# Schematic1.net
KiCad netlist of a schematic drawn in Altium Designer
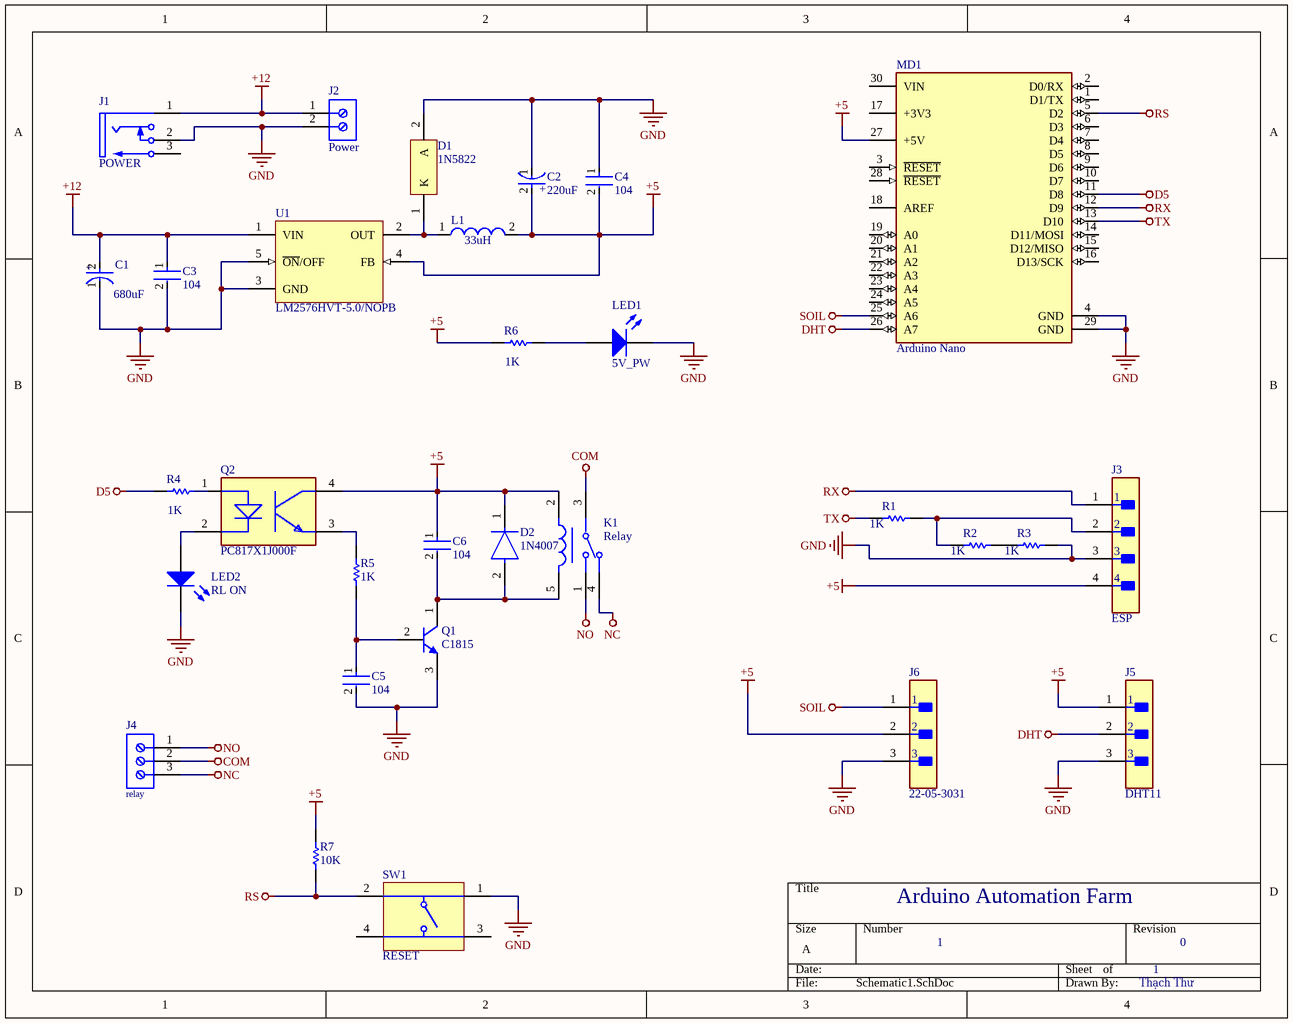
[diagram p0: Schematic1.SchDoc]

(export (version "E")
  (design (tool "Eeschema 10.0.6"))
  (components
    (comp (ref "C1")
      (value "680uF")
      (footprint "FP-RAD-TH-D_12_5_0_5-L_30-MFG")
      (description "Aluminum Electrolytic Capacitors (Radial Lead Type) AEC-Q200 Qualified 680uF ±20% 50V")
      (fields (field (name "VOLTAGE") "50V") (field (name "TOLERANCE") "20%"))
      (libsource (lib "Altium Content Vault") (part "203bc49f2ac43e59fd269a8c329ed05"))
    )
    (comp (ref "C2")
      (value "220uF")
      (footprint "FP-RAD-TH-D_8_0_5-L_11_5-MFG")
      (description "Aluminum Electrolytic Capacitors (Radial Lead Type) 220uF ±20% 25V")
      (fields (field (name "VOLTAGE") "25V") (field (name "TOLERANCE") "20%"))
      (libsource (lib "Altium Content Vault") (part "a00bbbee19879c290e62620ae7e47b1"))
    )
    (comp (ref "C3")
      (value "104")
      (footprint "FP-RCE1A2-MFG")
      (description "Cap Ceramic 100nF 100V X7R ±10% Radial 2.5mm +125°C Automotive Ammo Pack")
      (fields (field (name "TOLERANCE") "10%"))
      (libsource (lib "Altium Content Vault") (part "02cd4be3c70576c341d710602a673aa"))
    )
    (comp (ref "C4")
      (value "104")
      (footprint "FP-RCE1A2-MFG")
      (description "Cap Ceramic 100nF 100V X7R ±10% Radial 2.5mm +125°C Automotive Ammo Pack")
      (fields (field (name "TOLERANCE") "10%"))
      (libsource (lib "Altium Content Vault") (part "02cd4be3c70576c341d710602a673aa"))
    )
    (comp (ref "C5")
      (value "104")
      (footprint "FP-RCE1A2-MFG")
      (description "Cap Ceramic 100nF 100V X7R ±10% Radial 2.5mm +125°C Automotive Ammo Pack")
      (fields (field (name "TOLERANCE") "10%"))
      (libsource (lib "Altium Content Vault") (part "02cd4be3c70576c341d710602a673aa"))
    )
    (comp (ref "C6")
      (value "104")
      (footprint "FP-RCE1A2-MFG")
      (description "Cap Ceramic 100nF 100V X7R ±10% Radial 2.5mm +125°C Automotive Ammo Pack")
      (fields (field (name "TOLERANCE") "10%"))
      (libsource (lib "Altium Content Vault") (part "02cd4be3c70576c341d710602a673aa"))
    )
    (comp (ref "D1")
      (value "1N5822")
      (footprint "ONSC-AXIAL_LEAD-2-267-05_V")
      (description "Rectifier, 2-Pin Axial_Lead, Bulk Bag")
      (fields (field (name "MANUFACTURER") "On Semiconductor"))
      (libsource (lib "Altium Content Vault") (part "ONSC-D-K1A2-2_A"))
    )
    (comp (ref "D2")
      (value "1N4007")
      (footprint "FP-1N4007-MFG")
      (description "Rectifier diode 1000 V 1 A DO-41, ,")
      (fields
        (field (name "MANUFACTURER") "Diotec")
        (field (name "OCTOPART") "https://octopart.com/1n4007-diotec-4040411")
      )
      (libsource (lib "Altium Content Vault") (part "d7152d700b627762746794eb795d46e"))
    )
    (comp (ref "J1")
      (value "POWER")
      (footprint "SWITCH-RAPC712X-3_V")
      (description "Conn Powerjack Mini R/A PCMT, 5 A, 3-Pin THD, RoHS")
      (fields (field (name "MANUFACTURER") "Switchcraft"))
      (libsource (lib "Altium Content Vault") (part "SWITCH-RAPC712X-3"))
    )
    (comp (ref "J2")
      (value "Power")
      (footprint "691102710002")
      (description "Series 102 - 5.00 mm Horizontal Entry Modular with Pressure Clamp WR-TBL, 2 pin")
      (fields
        (field (name "MANUFACTURER") "Wurth Elektronik")
        (field (name "PART NUMBER") "691102710002")
        (field (name "PUBLISHER") "WurthElektronik")
      )
      (libsource (lib "Altium Content Vault") (part "WE-CN-1P-F-TB2"))
    )
    (comp (ref "J3")
      (value "ESP")
      (footprint "FP-110990030-MFG")
      (description "GROVE 2MM 4PIN VERT CONN 10PCS")
      (libsource (lib "Altium Content Vault") (part "299a8cea1bdcbc3624fe62c390fa72c"))
    )
    (comp (ref "J4")
      (value "relay")
      (footprint "691101710003")
      (description "Series 101 - 5.00 mm Horizontal Entry Modular with Pressure Clamp WR-TBL, 3 pin")
      (fields
        (field (name "PART NUMBER") "691101710003")
        (field (name "MANUFACTURER") "Wurth Elektronik")
        (field (name "PUBLISHER") "WurthElektronik")
      )
      (libsource (lib "Altium Content Vault") (part "WE-CN-1P-F-TB3"))
    )
    (comp (ref "J5")
      (value "DHT11")
      (footprint "FP-22-28-4030-MFG")
      (description "CONN HEADER VERT 3POS 2.54MM")
      (fields
        (field (name "MANUFACTURER PART NUMBER") "22-28-4030")
        (field (name "OCTOPART") "https://octopart.com/0022284030-molex-10476094")
      )
      (libsource (lib "Altium Content Vault") (part "0d3f023dd272f625e17a2be33dea85f"))
    )
    (comp (ref "J6")
      (value "22-05-3031")
      (footprint "FP-22-05-3031-MFG")
      (description "CONN HEADER R/A 3POS 2.54MM")
      (libsource (lib "Altium Content Vault") (part "0d3f023dd272f625e17a2be33dea85f"))
    )
    (comp (ref "K1")
      (value "Relay")
      (footprint "FP-1-1721150-0-MFG")
      (description "RELAY GEN PURPOSE SPDT 10A 5V")
      (fields
        (field (name "MANUFACTURER") "TE")
        (field (name "OCTOPART") "https://octopart.com/1-1721150-0-te+connectivity-41294869")
      )
      (libsource (lib "Altium Content Vault") (part "6d7f6cec76f9d90da65a396cf24d809"))
    )
    (comp (ref "L1")
      (value "33uH")
      (footprint "WE-TI-L")
      (description "Radial Leaded Wire Wound Inductor WE-TI, L=330 µH")
      (fields (field (name "PARTNUMBER") "744772331") (field (name "MANUFACTURER") "Wuerth Elektronik"))
      (libsource (lib "Altium Content Vault") (part "PAS-IND-INDUCTOR-2"))
    )
    (comp (ref "LED1")
      (value "5V_PW")
      (footprint "Type 5mm")
      (description "THT LED round mono-color color lens, WL-TMRW, Blue")
      (fields (field (name "MANUFACTURER") "Wuerth Elektronik") (field (name "PARTNUMBER") "151051BS04000"))
      (libsource (lib "Altium Content Vault") (part "WE-LED_K1A2-2"))
    )
    (comp (ref "LED2")
      (value "RL ON")
      (footprint "Type 5mm")
      (description "THT LED round mono-color color lens, WL-TMRW, Blue")
      (fields (field (name "MANUFACTURER") "Wuerth Elektronik") (field (name "PARTNUMBER") "151051BS04000"))
      (libsource (lib "Altium Content Vault") (part "WE-LED_K1A2-2"))
    )
    (comp (ref "MD1")
      (value "Arduino Nano")
      (footprint "FP-A000005-MFG")
      (description "ARDUINO NANO ATMEGA328 EVAL BRD")
      (libsource (lib "Altium Content Vault") (part "d190c066e99afd1c6882cf92e11b2cc"))
    )
    (comp (ref "Q1")
      (value "C1815")
      (footprint "TO-226-AA")
      (description "NPN Bipolar Transistor")
      (fields (field (name "PUBLISHER") "Altium Limited"))
      (libsource (lib "Miscellaneous Devices") (part "NPN"))
    )
    (comp (ref "Q2")
      (value "PC817X1J000F")
      (footprint "FP-PC817X1J000F-MFG")
      (description "OPTOISOLATOR 5KV TRANS 4DIP")
      (libsource (lib "Altium Content Vault") (part "8d9d817270a4e8f0d794346117f6aa3"))
    )
    (comp (ref "R1")
      (value "1K")
      (footprint "AXIAL-0.3")
      (description "Resistor")
      (fields (field (name "Comment") "Res1") (field (name "PUBLISHER") "Altium Limited"))
      (libsource (lib "Miscellaneous Devices") (part "Res1"))
    )
    (comp (ref "R2")
      (value "1K")
      (footprint "AXIAL-0.3")
      (description "Resistor")
      (fields (field (name "Comment") "Res1") (field (name "PUBLISHER") "Altium Limited"))
      (libsource (lib "Miscellaneous Devices") (part "Res1"))
    )
    (comp (ref "R3")
      (value "1K")
      (footprint "AXIAL-0.3")
      (description "Resistor")
      (fields (field (name "Comment") "Res1") (field (name "PUBLISHER") "Altium Limited"))
      (libsource (lib "Miscellaneous Devices") (part "Res1"))
    )
    (comp (ref "R4")
      (value "1K")
      (footprint "AXIAL-0.3")
      (description "Resistor")
      (fields (field (name "Comment") "Res1") (field (name "PUBLISHER") "Altium Limited"))
      (libsource (lib "Miscellaneous Devices") (part "Res1"))
    )
    (comp (ref "R5")
      (value "1K")
      (footprint "AXIAL-0.3")
      (description "Resistor")
      (fields (field (name "Comment") "Res1") (field (name "PUBLISHER") "Altium Limited"))
      (libsource (lib "Miscellaneous Devices") (part "Res1"))
    )
    (comp (ref "R6")
      (value "1K")
      (footprint "AXIAL-0.3")
      (description "Resistor")
      (fields (field (name "Comment") "Res1") (field (name "PUBLISHER") "Altium Limited"))
      (libsource (lib "Miscellaneous Devices") (part "Res1"))
    )
    (comp (ref "R7")
      (value "10K")
      (footprint "AXIAL-0.3")
      (description "Resistor")
      (fields (field (name "PUBLISHER") "Altium Limited"))
      (libsource (lib "Miscellaneous Devices") (part "Res1"))
    )
    (comp (ref "SW1")
      (value "RESET")
      (footprint "TECO-1825910-6_V")
      (description "Tact Switch, SPST-NO, 0.05 A, -35 to 85 degC, 4-Pin THD, RoHS, Bulk")
      (fields (field (name "PART NO") "1825910-6") (field (name "MANUFACTURER") "TE Connectivity"))
      (libsource (lib "Altium Content Vault") (part "SW-SPST-4_A"))
    )
    (comp (ref "U1")
      (value "LM2576HVT-5.0/NOPB")
      (footprint "KC0005A")
      (description "SIMPLE SWITCHER® 3A Step-Down Voltage Regulator, 5-pin TO-220, Pb-Free")
      (fields (field (name "MANUFACTURER") "Texas Instruments"))
      (libsource (lib "Altium Content Vault") (part "PM-REG-LM2575HVT-12"))
    )
  )
  (nets
    (net (code "1") (name "+5") (class "Default")
      (node (ref "C2") (pin "2") (pinfunction "A_2") (pintype "passive"))
      (node (ref "C4") (pin "2") (pinfunction "2_2") (pintype "passive"))
      (node (ref "C6") (pin "1") (pinfunction "1_1") (pintype "passive"))
      (node (ref "D2") (pin "1") (pinfunction "C_1") (pintype "passive"))
      (node (ref "J3") (pin "4") (pinfunction "4_4") (pintype "passive"))
      (node (ref "J5") (pin "1") (pinfunction "1_1") (pintype "passive"))
      (node (ref "J6") (pin "2") (pinfunction "2_2") (pintype "passive"))
      (node (ref "K1") (pin "2") (pinfunction "2_2") (pintype "passive"))
      (node (ref "L1") (pin "2") (pinfunction "2_2") (pintype "passive"))
      (node (ref "MD1") (pin "27") (pinfunction "+5V_27") (pintype "power_in"))
      (node (ref "Q2") (pin "4") (pinfunction "C_4") (pintype "passive"))
      (node (ref "R6") (pin "2") (pinfunction "2_2") (pintype "passive"))
      (node (ref "R7") (pin "1") (pinfunction "1_1") (pintype "passive"))
      (node (ref "U1") (pin "4") (pinfunction "FB_4") (pintype "input"))
    )
    (net (code "2") (name "+12") (class "Default")
      (node (ref "C1") (pin "2") (pinfunction "A_2") (pintype "passive"))
      (node (ref "C3") (pin "1") (pinfunction "1_1") (pintype "passive"))
      (node (ref "J1") (pin "1") (pinfunction "1_1") (pintype "passive"))
      (node (ref "J2") (pin "1") (pinfunction "1_1") (pintype "passive"))
      (node (ref "U1") (pin "1") (pinfunction "VIN_1") (pintype "power_in"))
    )
    (net (code "3") (name "COM") (class "Default")
      (node (ref "J4") (pin "2") (pinfunction "2_2") (pintype "passive"))
      (node (ref "K1") (pin "3") (pinfunction "3_3") (pintype "passive"))
    )
    (net (code "4") (name "D5") (class "Default")
      (node (ref "MD1") (pin "11") (pinfunction "D8_11") (pintype "bidirectional"))
      (node (ref "R4") (pin "2") (pinfunction "2_2") (pintype "passive"))
    )
    (net (code "5") (name "DHT") (class "Default")
      (node (ref "J5") (pin "2") (pinfunction "2_2") (pintype "passive"))
      (node (ref "MD1") (pin "26") (pinfunction "A7_26") (pintype "bidirectional"))
    )
    (net (code "6") (name "GND") (class "Default")
      (node (ref "C1") (pin "1") (pinfunction "C_1") (pintype "passive"))
      (node (ref "C2") (pin "1") (pinfunction "C_1") (pintype "passive"))
      (node (ref "C3") (pin "2") (pinfunction "2_2") (pintype "passive"))
      (node (ref "C4") (pin "1") (pinfunction "1_1") (pintype "passive"))
      (node (ref "C5") (pin "2") (pinfunction "2_2") (pintype "passive"))
      (node (ref "D1") (pin "2") (pinfunction "A_2") (pintype "passive"))
      (node (ref "J1") (pin "2") (pinfunction "2_2") (pintype "passive"))
      (node (ref "J2") (pin "2") (pinfunction "2_2") (pintype "passive"))
      (node (ref "J3") (pin "3") (pinfunction "3_3") (pintype "passive"))
      (node (ref "J5") (pin "3") (pinfunction "3_3") (pintype "passive"))
      (node (ref "J6") (pin "3") (pinfunction "3_3") (pintype "passive"))
      (node (ref "LED1") (pin "1") (pinfunction "K_1") (pintype "passive"))
      (node (ref "LED2") (pin "1") (pinfunction "K_1") (pintype "passive"))
      (node (ref "MD1") (pin "29") (pinfunction "GND_29") (pintype "power_in"))
      (node (ref "MD1") (pin "4") (pinfunction "GND_4") (pintype "power_in"))
      (node (ref "Q1") (pin "3") (pinfunction "E_3") (pintype "passive"))
      (node (ref "R3") (pin "1") (pinfunction "1_1") (pintype "passive"))
      (node (ref "SW1") (pin "1") (pinfunction "1_1") (pintype "passive"))
      (node (ref "U1") (pin "3") (pinfunction "GND_3") (pintype "power_in"))
      (node (ref "U1") (pin "5") (pinfunction "~{ON}/OFF_5") (pintype "input"))
    )
    (net (code "7") (name "NC") (class "Default")
      (node (ref "J4") (pin "3") (pinfunction "3_3") (pintype "passive"))
      (node (ref "K1") (pin "4") (pinfunction "4_4") (pintype "passive"))
    )
    (net (code "8") (name "NO") (class "Default")
      (node (ref "J4") (pin "1") (pinfunction "1_1") (pintype "passive"))
      (node (ref "K1") (pin "1") (pinfunction "1_1") (pintype "passive"))
    )
    (net (code "9") (name "Net-(D1-K)") (class "Default")
      (node (ref "D1") (pin "1") (pinfunction "K_1") (pintype "passive"))
      (node (ref "L1") (pin "1") (pinfunction "1_1") (pintype "passive"))
      (node (ref "U1") (pin "2") (pinfunction "OUT_2") (pintype "power_in"))
    )
    (net (code "10") (name "Net-(D2-A)") (class "Default")
      (node (ref "C6") (pin "2") (pinfunction "2_2") (pintype "passive"))
      (node (ref "D2") (pin "2") (pinfunction "A_2") (pintype "passive"))
      (node (ref "K1") (pin "5") (pinfunction "5_5") (pintype "passive"))
      (node (ref "Q1") (pin "1") (pinfunction "C_1") (pintype "passive"))
    )
    (net (code "11") (name "Net-(J3-Pad2)") (class "Default")
      (node (ref "J3") (pin "2") (pinfunction "2_2") (pintype "passive"))
      (node (ref "R1") (pin "1") (pinfunction "1_1") (pintype "passive"))
      (node (ref "R2") (pin "2") (pinfunction "2_2") (pintype "passive"))
    )
    (net (code "12") (name "Net-(LED1-A)") (class "Default")
      (node (ref "LED1") (pin "2") (pinfunction "A_2") (pintype "passive"))
      (node (ref "R6") (pin "1") (pinfunction "1_1") (pintype "passive"))
    )
    (net (code "13") (name "Net-(LED2-A)") (class "Default")
      (node (ref "LED2") (pin "2") (pinfunction "A_2") (pintype "passive"))
      (node (ref "Q2") (pin "2") (pinfunction "C_2") (pintype "passive"))
    )
    (net (code "14") (name "Net-(Q1-B)") (class "Default")
      (node (ref "C5") (pin "1") (pinfunction "1_1") (pintype "passive"))
      (node (ref "Q1") (pin "2") (pinfunction "B_2") (pintype "passive"))
      (node (ref "R5") (pin "2") (pinfunction "2_2") (pintype "passive"))
    )
    (net (code "15") (name "Net-(Q2-A)") (class "Default")
      (node (ref "Q2") (pin "1") (pinfunction "A_1") (pintype "passive"))
      (node (ref "R4") (pin "1") (pinfunction "1_1") (pintype "passive"))
    )
    (net (code "16") (name "Net-(Q2-E)") (class "Default")
      (node (ref "Q2") (pin "3") (pinfunction "E_3") (pintype "passive"))
      (node (ref "R5") (pin "1") (pinfunction "1_1") (pintype "passive"))
    )
    (net (code "17") (name "Net-(R2-Pad1)") (class "Default")
      (node (ref "R2") (pin "1") (pinfunction "1_1") (pintype "passive"))
      (node (ref "R3") (pin "2") (pinfunction "2_2") (pintype "passive"))
    )
    (net (code "18") (name "RS") (class "Default")
      (node (ref "MD1") (pin "5") (pinfunction "D2_5") (pintype "bidirectional"))
      (node (ref "R7") (pin "2") (pinfunction "2_2") (pintype "passive"))
      (node (ref "SW1") (pin "2") (pinfunction "2_2") (pintype "passive"))
    )
    (net (code "19") (name "RX") (class "Default")
      (node (ref "J3") (pin "1") (pinfunction "1_1") (pintype "passive"))
      (node (ref "MD1") (pin "12") (pinfunction "D9_12") (pintype "bidirectional"))
    )
    (net (code "20") (name "SOIL") (class "Default")
      (node (ref "J6") (pin "1") (pinfunction "1_1") (pintype "passive"))
      (node (ref "MD1") (pin "25") (pinfunction "A6_25") (pintype "bidirectional"))
    )
    (net (code "21") (name "TX") (class "Default")
      (node (ref "MD1") (pin "13") (pinfunction "D10_13") (pintype "bidirectional"))
      (node (ref "R1") (pin "2") (pinfunction "2_2") (pintype "passive"))
    )
    (net (code "22") (name "unconnected-(J1-Pad3)") (class "Default")
      (node (ref "J1") (pin "3") (pinfunction "3_3") (pintype "passive"))
    )
    (net (code "23") (name "unconnected-(MD1-+3V3-Pad17)") (class "Default")
      (node (ref "MD1") (pin "17") (pinfunction "+3V3_17") (pintype "power_in"))
    )
    (net (code "24") (name "unconnected-(MD1-A0-Pad19)") (class "Default")
      (node (ref "MD1") (pin "19") (pinfunction "A0_19") (pintype "bidirectional"))
    )
    (net (code "25") (name "unconnected-(MD1-A1-Pad20)") (class "Default")
      (node (ref "MD1") (pin "20") (pinfunction "A1_20") (pintype "bidirectional"))
    )
    (net (code "26") (name "unconnected-(MD1-A2-Pad21)") (class "Default")
      (node (ref "MD1") (pin "21") (pinfunction "A2_21") (pintype "bidirectional"))
    )
    (net (code "27") (name "unconnected-(MD1-A3-Pad22)") (class "Default")
      (node (ref "MD1") (pin "22") (pinfunction "A3_22") (pintype "bidirectional"))
    )
    (net (code "28") (name "unconnected-(MD1-A4-Pad23)") (class "Default")
      (node (ref "MD1") (pin "23") (pinfunction "A4_23") (pintype "bidirectional"))
    )
    (net (code "29") (name "unconnected-(MD1-A5-Pad24)") (class "Default")
      (node (ref "MD1") (pin "24") (pinfunction "A5_24") (pintype "bidirectional"))
    )
    (net (code "30") (name "unconnected-(MD1-AREF-Pad18)") (class "Default")
      (node (ref "MD1") (pin "18") (pinfunction "AREF_18") (pintype "passive"))
    )
    (net (code "31") (name "unconnected-(MD1-D0{slash}RX-Pad2)") (class "Default")
      (node (ref "MD1") (pin "2") (pinfunction "D0/RX_2") (pintype "bidirectional"))
    )
    (net (code "32") (name "unconnected-(MD1-D1{slash}TX-Pad1)") (class "Default")
      (node (ref "MD1") (pin "1") (pinfunction "D1/TX_1") (pintype "bidirectional"))
    )
    (net (code "33") (name "unconnected-(MD1-D3-Pad6)") (class "Default")
      (node (ref "MD1") (pin "6") (pinfunction "D3_6") (pintype "bidirectional"))
    )
    (net (code "34") (name "unconnected-(MD1-D4-Pad7)") (class "Default")
      (node (ref "MD1") (pin "7") (pinfunction "D4_7") (pintype "bidirectional"))
    )
    (net (code "35") (name "unconnected-(MD1-D5-Pad8)") (class "Default")
      (node (ref "MD1") (pin "8") (pinfunction "D5_8") (pintype "bidirectional"))
    )
    (net (code "36") (name "unconnected-(MD1-D6-Pad9)") (class "Default")
      (node (ref "MD1") (pin "9") (pinfunction "D6_9") (pintype "bidirectional"))
    )
    (net (code "37") (name "unconnected-(MD1-D7-Pad10)") (class "Default")
      (node (ref "MD1") (pin "10") (pinfunction "D7_10") (pintype "bidirectional"))
    )
    (net (code "38") (name "unconnected-(MD1-D11{slash}MOSI-Pad14)") (class "Default")
      (node (ref "MD1") (pin "14") (pinfunction "D11/MOSI_14") (pintype "bidirectional"))
    )
    (net (code "39") (name "unconnected-(MD1-D12{slash}MISO-Pad15)") (class "Default")
      (node (ref "MD1") (pin "15") (pinfunction "D12/MISO_15") (pintype "bidirectional"))
    )
    (net (code "40") (name "unconnected-(MD1-D13{slash}SCK-Pad16)") (class "Default")
      (node (ref "MD1") (pin "16") (pinfunction "D13/SCK_16") (pintype "bidirectional"))
    )
    (net (code "41") (name "unconnected-(MD1-VIN-Pad30)") (class "Default")
      (node (ref "MD1") (pin "30") (pinfunction "VIN_30") (pintype "power_in"))
    )
    (net (code "42") (name "unconnected-(MD1-~{RESET}-Pad3)") (class "Default")
      (node (ref "MD1") (pin "3") (pinfunction "~{RESET}_3") (pintype "input"))
    )
    (net (code "43") (name "unconnected-(MD1-~{RESET}-Pad28)") (class "Default")
      (node (ref "MD1") (pin "28") (pinfunction "~{RESET}_28") (pintype "input"))
    )
    (net (code "44") (name "unconnected-(SW1-Pad3)") (class "Default")
      (node (ref "SW1") (pin "3") (pinfunction "3_3") (pintype "passive"))
    )
    (net (code "45") (name "unconnected-(SW1-Pad4)") (class "Default")
      (node (ref "SW1") (pin "4") (pinfunction "4_4") (pintype "passive"))
    )
  )
)
